# power.net
KiCad netlist of a schematic drawn in Altium Designer
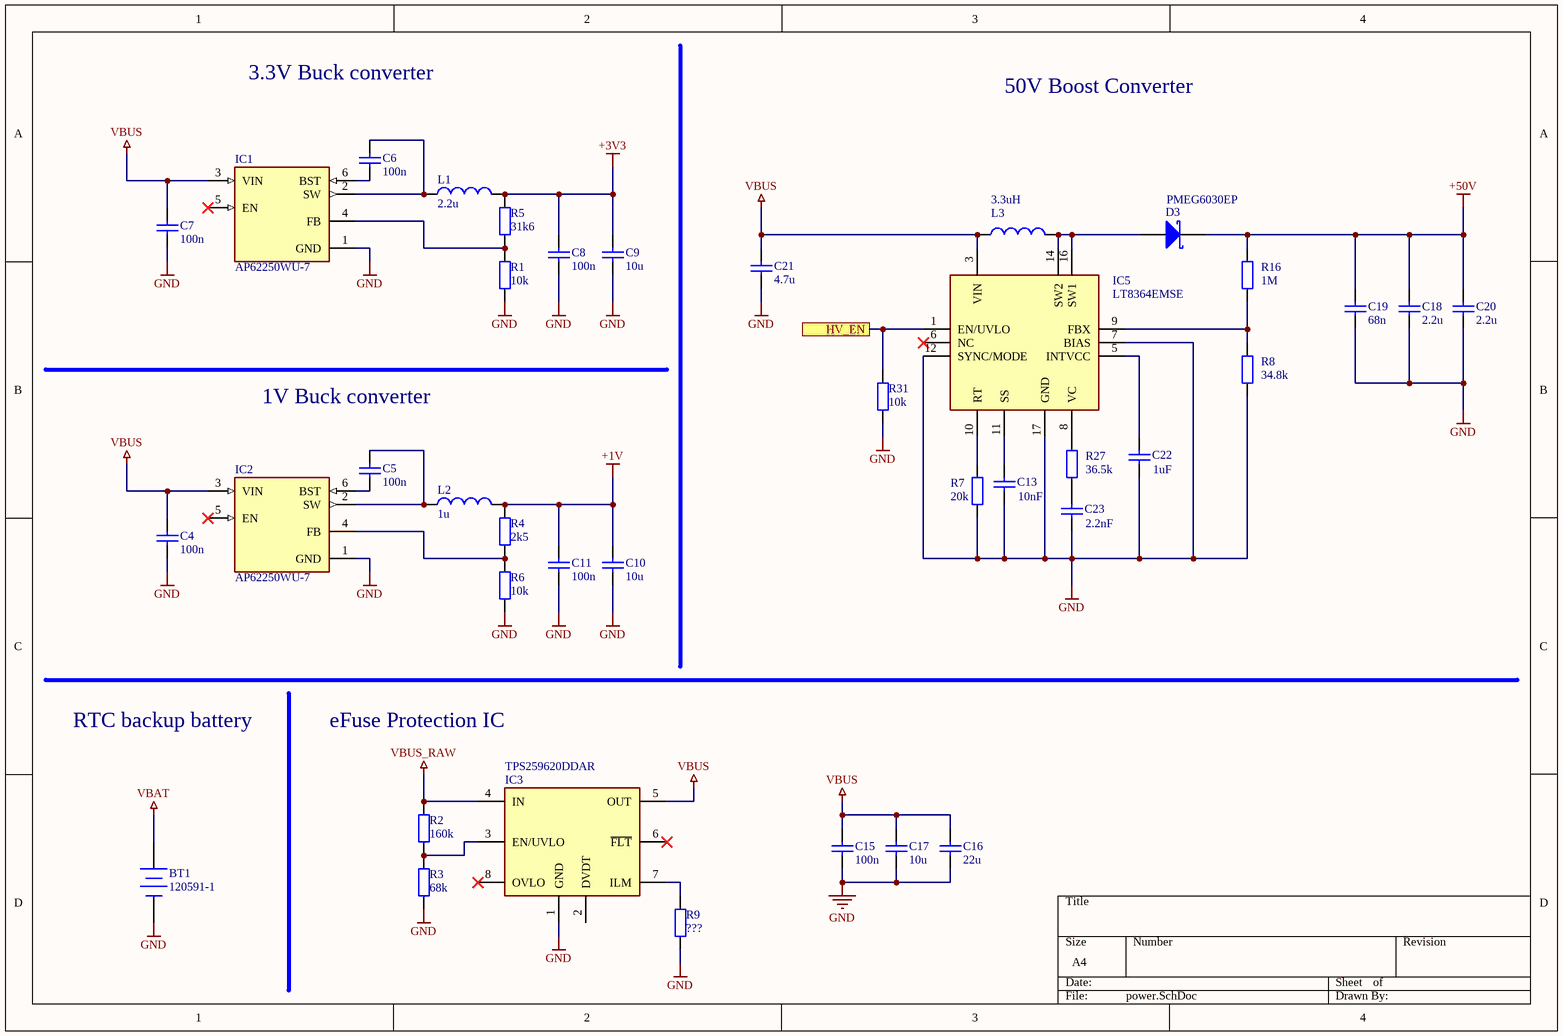
[diagram p0: power.SchDoc]

(export (version "E")
  (design (tool "Eeschema 10.0.6"))
  (components
    (comp (ref "BT1")
      (value "120591-1")
      (footprint "Lib_VFD_Clock:BR1220_Horizontal")
      (description "Battery")
      (fields (field (name "MOUSER PART NUMBER") "571-1205911"))
      (libsource (lib "Lib_VFD_Clock") (part "120591-1"))
    )
    (comp (ref "C4")
      (value "100n")
      (footprint "Miscellaneous Devices:1608[0603]")
      (description "Capacitor")
      (fields (field (name "PUBLISHER") "Altium Limited"))
      (libsource (lib "Miscellaneous Devices") (part "Cap"))
    )
    (comp (ref "C5")
      (value "100n")
      (footprint "Miscellaneous Devices:1608[0603]")
      (description "Capacitor")
      (fields (field (name "PUBLISHER") "Altium Limited"))
      (libsource (lib "Miscellaneous Devices") (part "Cap"))
    )
    (comp (ref "C6")
      (value "100n")
      (footprint "Miscellaneous Devices:1608[0603]")
      (description "Capacitor")
      (fields (field (name "PUBLISHER") "Altium Limited"))
      (libsource (lib "Miscellaneous Devices") (part "Cap"))
    )
    (comp (ref "C7")
      (value "100n")
      (footprint "Miscellaneous Devices:1608[0603]")
      (description "Capacitor")
      (fields (field (name "PUBLISHER") "Altium Limited"))
      (libsource (lib "Miscellaneous Devices") (part "Cap"))
    )
    (comp (ref "C8")
      (value "100n")
      (footprint "Miscellaneous Devices:1608[0603]")
      (description "Capacitor")
      (fields (field (name "PUBLISHER") "Altium Limited"))
      (libsource (lib "Miscellaneous Devices") (part "Cap"))
    )
    (comp (ref "C9")
      (value "10u")
      (footprint "Miscellaneous Devices:1608[0603]")
      (description "Capacitor")
      (fields (field (name "PUBLISHER") "Altium Limited"))
      (libsource (lib "Miscellaneous Devices") (part "Cap"))
    )
    (comp (ref "C10")
      (value "10u")
      (footprint "Miscellaneous Devices:1608[0603]")
      (description "Capacitor")
      (fields (field (name "PUBLISHER") "Altium Limited"))
      (libsource (lib "Miscellaneous Devices") (part "Cap"))
    )
    (comp (ref "C11")
      (value "100n")
      (footprint "Miscellaneous Devices:1608[0603]")
      (description "Capacitor")
      (fields (field (name "PUBLISHER") "Altium Limited"))
      (libsource (lib "Miscellaneous Devices") (part "Cap"))
    )
    (comp (ref "C13")
      (value "10nF")
      (footprint "Miscellaneous Devices:1608[0603]")
      (description "Capacitor")
      (fields (field (name "PUBLISHER") "Altium Limited"))
      (libsource (lib "Miscellaneous Devices") (part "Cap"))
    )
    (comp (ref "C15")
      (value "100n")
      (footprint "Miscellaneous Devices:1608[0603]")
      (description "Capacitor")
      (fields (field (name "PUBLISHER") "Altium Limited"))
      (libsource (lib "Miscellaneous Devices") (part "Cap"))
    )
    (comp (ref "C16")
      (value "22u")
      (footprint "Miscellaneous Devices:1608[0603]")
      (description "Capacitor")
      (fields (field (name "PUBLISHER") "Altium Limited"))
      (libsource (lib "Miscellaneous Devices") (part "Cap"))
    )
    (comp (ref "C17")
      (value "10u")
      (footprint "Miscellaneous Devices:1608[0603]")
      (description "Capacitor")
      (fields (field (name "PUBLISHER") "Altium Limited"))
      (libsource (lib "Miscellaneous Devices") (part "Cap"))
    )
    (comp (ref "C18")
      (value "2.2u")
      (footprint "Miscellaneous Devices:C1210")
      (description "Capacitor")
      (fields (field (name "PUBLISHER") "Altium Limited"))
      (libsource (lib "Miscellaneous Devices") (part "Cap"))
    )
    (comp (ref "C19")
      (value "68n")
      (footprint "Miscellaneous Devices:1608[0603]")
      (description "Capacitor")
      (fields (field (name "PUBLISHER") "Altium Limited"))
      (libsource (lib "Miscellaneous Devices") (part "Cap"))
    )
    (comp (ref "C20")
      (value "2.2u")
      (footprint "Miscellaneous Devices:C1210")
      (description "Capacitor")
      (fields (field (name "PUBLISHER") "Altium Limited"))
      (libsource (lib "Miscellaneous Devices") (part "Cap"))
    )
    (comp (ref "C21")
      (value "4.7u")
      (footprint "Miscellaneous Devices:1608[0603]")
      (description "Capacitor")
      (fields (field (name "PUBLISHER") "Altium Limited"))
      (libsource (lib "Miscellaneous Devices") (part "Cap"))
    )
    (comp (ref "C22")
      (value "1uF")
      (footprint "Miscellaneous Devices:1608[0603]")
      (description "Capacitor")
      (fields (field (name "PUBLISHER") "Altium Limited"))
      (libsource (lib "Miscellaneous Devices") (part "Cap"))
    )
    (comp (ref "C23")
      (value "2.2nF")
      (footprint "Miscellaneous Devices:1608[0603]")
      (description "Capacitor")
      (fields (field (name "PUBLISHER") "Altium Limited"))
      (libsource (lib "Miscellaneous Devices") (part "Cap"))
    )
    (comp (ref "D3")
      (value "PMEG6030EP")
      (footprint "PMEG6030EP115")
      (description "Schottky Diode")
      (fields (field (name "PUBLISHER") "Altium Limited"))
      (libsource (lib "Lib_VFD_Clock") (part "PMEG6030EP"))
    )
    (comp (ref "IC1")
      (value "AP62250WU-7")
      (footprint "TSOT26")
      (description "Integrated Circuit")
      (fields (field (name "MOUSER PART NUMBER") "621-AP62250WU-7"))
      (libsource (lib "Lib_VFD_Clock") (part "AP62250WU-7"))
    )
    (comp (ref "IC2")
      (value "AP62250WU-7")
      (footprint "TSOT26")
      (description "Integrated Circuit")
      (fields (field (name "MOUSER PART NUMBER") "621-AP62250WU-7"))
      (libsource (lib "Lib_VFD_Clock") (part "AP62250WU-7"))
    )
    (comp (ref "IC3")
      (value "TPS259620DDAR")
      (footprint "Lib_VFD_Clock:SOIC127P600X170-9N")
      (description "Integrated Circuit")
      (fields (field (name "MOUSER PART NUMBER") "595-TPS259620DDAR"))
      (libsource (lib "Lib_VFD_Clock") (part "TPS259620DDAR"))
    )
    (comp (ref "IC5")
      (value "LT8364EMSE")
      (footprint "Lib_VFD_Clock:LT8364EMSEPBF")
      (description "Integrated Circuit")
      (fields
        (field (name "MANUFACTURER_PART_NUMBER") "LT8364EMSE#PBF")
        (field (name "MOUSER PART NUMBER") "584-LT8364EMSEPBF")
      )
      (libsource (lib "Lib_VFD_Clock") (part "LT8364EMSE#PBF"))
    )
    (comp (ref "L1")
      (value "2.2u")
      (footprint "Lib_VFD_Clock:BWVS004040182R2M00")
      (description "Inductor")
      (fields (field (name "PUBLISHER") "Altium Limited"))
      (libsource (lib "Miscellaneous Devices") (part "Inductor"))
    )
    (comp (ref "L2")
      (value "1u")
      (footprint "Lib_VFD_Clock:BWVS004040182R2M00")
      (description "Inductor")
      (fields (field (name "PUBLISHER") "Altium Limited"))
      (libsource (lib "Miscellaneous Devices") (part "Inductor"))
    )
    (comp (ref "L3")
      (value "3.3uH")
      (footprint "Lib_VFD_Clock:BWVS004040182R2M00")
      (description "Inductor")
      (fields (field (name "PUBLISHER") "Altium Limited"))
      (libsource (lib "Miscellaneous Devices") (part "Inductor"))
    )
    (comp (ref "R1")
      (value "10k")
      (footprint "Miscellaneous Devices:J1-0603")
      (description "Resistor")
      (fields (field (name "PUBLISHER") "Altium Limited"))
      (libsource (lib "Miscellaneous Devices") (part "Res2"))
    )
    (comp (ref "R2")
      (value "160k")
      (footprint "Miscellaneous Devices:J1-0603")
      (description "Resistor")
      (fields (field (name "PUBLISHER") "Altium Limited"))
      (libsource (lib "Miscellaneous Devices") (part "Res2"))
    )
    (comp (ref "R3")
      (value "68k")
      (footprint "Miscellaneous Devices:J1-0603")
      (description "Resistor")
      (fields (field (name "PUBLISHER") "Altium Limited"))
      (libsource (lib "Miscellaneous Devices") (part "Res2"))
    )
    (comp (ref "R4")
      (value "2k5")
      (footprint "Miscellaneous Devices:J1-0603")
      (description "Resistor")
      (fields (field (name "PUBLISHER") "Altium Limited"))
      (libsource (lib "Miscellaneous Devices") (part "Res2"))
    )
    (comp (ref "R5")
      (value "31k6")
      (footprint "Miscellaneous Devices:J1-0603")
      (description "Resistor")
      (fields (field (name "PUBLISHER") "Altium Limited"))
      (libsource (lib "Miscellaneous Devices") (part "Res2"))
    )
    (comp (ref "R6")
      (value "10k")
      (footprint "Miscellaneous Devices:J1-0603")
      (description "Resistor")
      (fields (field (name "PUBLISHER") "Altium Limited"))
      (libsource (lib "Miscellaneous Devices") (part "Res2"))
    )
    (comp (ref "R7")
      (value "20k")
      (footprint "Miscellaneous Devices:J1-0603")
      (description "Resistor")
      (fields (field (name "PUBLISHER") "Altium Limited"))
      (libsource (lib "Miscellaneous Devices") (part "Res2"))
    )
    (comp (ref "R8")
      (value "34.8k")
      (footprint "Miscellaneous Devices:J1-0603")
      (description "Resistor")
      (fields (field (name "PUBLISHER") "Altium Limited"))
      (libsource (lib "Miscellaneous Devices") (part "Res2"))
    )
    (comp (ref "R9")
      (value "???")
      (footprint "Miscellaneous Devices:J1-0603")
      (description "Resistor")
      (fields (field (name "PUBLISHER") "Altium Limited"))
      (libsource (lib "Miscellaneous Devices") (part "Res2"))
    )
    (comp (ref "R16")
      (value "1M")
      (footprint "Miscellaneous Devices:J1-0603")
      (description "Resistor")
      (fields (field (name "PUBLISHER") "Altium Limited"))
      (libsource (lib "Miscellaneous Devices") (part "Res2"))
    )
    (comp (ref "R27")
      (value "36.5k")
      (footprint "Miscellaneous Devices:J1-0603")
      (description "Resistor")
      (fields (field (name "PUBLISHER") "Altium Limited"))
      (libsource (lib "Miscellaneous Devices") (part "Res2"))
    )
    (comp (ref "R31")
      (value "10k")
      (footprint "Miscellaneous Devices:J1-0603")
      (description "Resistor")
      (fields (field (name "PUBLISHER") "Altium Limited"))
      (libsource (lib "Miscellaneous Devices") (part "Res2"))
    )
  )
  (nets
    (net (code "1") (name "+1V") (class "Default")
      (node (ref "C10") (pin "2") (pinfunction "2_2") (pintype "passive"))
      (node (ref "C11") (pin "2") (pinfunction "2_2") (pintype "passive"))
      (node (ref "L2") (pin "2") (pinfunction "2_2") (pintype "passive"))
      (node (ref "R4") (pin "2") (pinfunction "2_2") (pintype "passive"))
    )
    (net (code "2") (name "+3V3") (class "Default")
      (node (ref "C8") (pin "2") (pinfunction "2_2") (pintype "passive"))
      (node (ref "C9") (pin "2") (pinfunction "2_2") (pintype "passive"))
      (node (ref "L1") (pin "2") (pinfunction "2_2") (pintype "passive"))
      (node (ref "R5") (pin "2") (pinfunction "2_2") (pintype "passive"))
    )
    (net (code "3") (name "+50V") (class "Default")
      (node (ref "C18") (pin "2") (pinfunction "2_2") (pintype "passive"))
      (node (ref "C19") (pin "2") (pinfunction "2_2") (pintype "passive"))
      (node (ref "C20") (pin "2") (pinfunction "2_2") (pintype "passive"))
      (node (ref "D3") (pin "2") (pinfunction "K_2") (pintype "passive"))
      (node (ref "R16") (pin "2") (pinfunction "2_2") (pintype "passive"))
    )
    (net (code "4") (name "/HV_EN") (class "Default")
      (node (ref "IC5") (pin "1") (pinfunction "EN/UVLO_1") (pintype "passive"))
      (node (ref "R31") (pin "2") (pinfunction "2_2") (pintype "passive"))
    )
    (net (code "5") (name "GND") (class "Default")
      (node (ref "BT1") (pin "1") (pinfunction "1_1") (pintype "passive"))
      (node (ref "C10") (pin "1") (pinfunction "1_1") (pintype "passive"))
      (node (ref "C11") (pin "1") (pinfunction "1_1") (pintype "passive"))
      (node (ref "C13") (pin "1") (pinfunction "1_1") (pintype "passive"))
      (node (ref "C15") (pin "1") (pinfunction "1_1") (pintype "passive"))
      (node (ref "C16") (pin "1") (pinfunction "1_1") (pintype "passive"))
      (node (ref "C17") (pin "1") (pinfunction "1_1") (pintype "passive"))
      (node (ref "C18") (pin "1") (pinfunction "1_1") (pintype "passive"))
      (node (ref "C19") (pin "1") (pinfunction "1_1") (pintype "passive"))
      (node (ref "C20") (pin "1") (pinfunction "1_1") (pintype "passive"))
      (node (ref "C21") (pin "1") (pinfunction "1_1") (pintype "passive"))
      (node (ref "C22") (pin "1") (pinfunction "1_1") (pintype "passive"))
      (node (ref "C23") (pin "1") (pinfunction "1_1") (pintype "passive"))
      (node (ref "C4") (pin "1") (pinfunction "1_1") (pintype "passive"))
      (node (ref "C7") (pin "1") (pinfunction "1_1") (pintype "passive"))
      (node (ref "C8") (pin "1") (pinfunction "1_1") (pintype "passive"))
      (node (ref "C9") (pin "1") (pinfunction "1_1") (pintype "passive"))
      (node (ref "IC1") (pin "1") (pinfunction "GND_1") (pintype "power_in"))
      (node (ref "IC2") (pin "1") (pinfunction "GND_1") (pintype "power_in"))
      (node (ref "IC3") (pin "1") (pinfunction "GND_1") (pintype "passive"))
      (node (ref "IC5") (pin "12") (pinfunction "SYNC/MODE_12") (pintype "passive"))
      (node (ref "IC5") (pin "17") (pinfunction "GND_17") (pintype "passive"))
      (node (ref "IC5") (pin "7") (pinfunction "BIAS_7") (pintype "passive"))
      (node (ref "R1") (pin "1") (pinfunction "1_1") (pintype "passive"))
      (node (ref "R3") (pin "1") (pinfunction "1_1") (pintype "passive"))
      (node (ref "R31") (pin "1") (pinfunction "1_1") (pintype "passive"))
      (node (ref "R6") (pin "1") (pinfunction "1_1") (pintype "passive"))
      (node (ref "R7") (pin "1") (pinfunction "1_1") (pintype "passive"))
      (node (ref "R8") (pin "1") (pinfunction "1_1") (pintype "passive"))
      (node (ref "R9") (pin "1") (pinfunction "1_1") (pintype "passive"))
    )
    (net (code "6") (name "Net-(C23-Pad2)") (class "Default")
      (node (ref "C23") (pin "2") (pinfunction "2_2") (pintype "passive"))
      (node (ref "R27") (pin "1") (pinfunction "1_1") (pintype "passive"))
    )
    (net (code "7") (name "Net-(D3-A)") (class "Default")
      (node (ref "D3") (pin "1") (pinfunction "A_1") (pintype "passive"))
      (node (ref "IC5") (pin "14") (pinfunction "SW2_14") (pintype "passive"))
      (node (ref "IC5") (pin "16") (pinfunction "SW1_16") (pintype "passive"))
      (node (ref "L3") (pin "2") (pinfunction "2_2") (pintype "passive"))
    )
    (net (code "8") (name "Net-(IC1-BST)") (class "Default")
      (node (ref "C6") (pin "1") (pinfunction "1_1") (pintype "passive"))
      (node (ref "IC1") (pin "6") (pinfunction "BST_6") (pintype "input"))
    )
    (net (code "9") (name "Net-(IC1-FB)") (class "Default")
      (node (ref "IC1") (pin "4") (pinfunction "FB_4") (pintype "passive"))
      (node (ref "R1") (pin "2") (pinfunction "2_2") (pintype "passive"))
      (node (ref "R5") (pin "1") (pinfunction "1_1") (pintype "passive"))
    )
    (net (code "10") (name "Net-(IC1-SW)") (class "Default")
      (node (ref "C6") (pin "2") (pinfunction "2_2") (pintype "passive"))
      (node (ref "IC1") (pin "2") (pinfunction "SW_2") (pintype "output"))
      (node (ref "L1") (pin "1") (pinfunction "1_1") (pintype "passive"))
    )
    (net (code "11") (name "Net-(IC2-BST)") (class "Default")
      (node (ref "C5") (pin "1") (pinfunction "1_1") (pintype "passive"))
      (node (ref "IC2") (pin "6") (pinfunction "BST_6") (pintype "input"))
    )
    (net (code "12") (name "Net-(IC2-FB)") (class "Default")
      (node (ref "IC2") (pin "4") (pinfunction "FB_4") (pintype "passive"))
      (node (ref "R4") (pin "1") (pinfunction "1_1") (pintype "passive"))
      (node (ref "R6") (pin "2") (pinfunction "2_2") (pintype "passive"))
    )
    (net (code "13") (name "Net-(IC2-SW)") (class "Default")
      (node (ref "C5") (pin "2") (pinfunction "2_2") (pintype "passive"))
      (node (ref "IC2") (pin "2") (pinfunction "SW_2") (pintype "output"))
      (node (ref "L2") (pin "1") (pinfunction "1_1") (pintype "passive"))
    )
    (net (code "14") (name "Net-(IC3-EN{slash}UVLO)") (class "Default")
      (node (ref "IC3") (pin "3") (pinfunction "EN/UVLO_3") (pintype "passive"))
      (node (ref "R2") (pin "1") (pinfunction "1_1") (pintype "passive"))
      (node (ref "R3") (pin "2") (pinfunction "2_2") (pintype "passive"))
    )
    (net (code "15") (name "Net-(IC3-ILM)") (class "Default")
      (node (ref "IC3") (pin "7") (pinfunction "ILM_7") (pintype "passive"))
      (node (ref "R9") (pin "2") (pinfunction "2_2") (pintype "passive"))
    )
    (net (code "16") (name "Net-(IC5-FBX)") (class "Default")
      (node (ref "IC5") (pin "9") (pinfunction "FBX_9") (pintype "passive"))
      (node (ref "R16") (pin "1") (pinfunction "1_1") (pintype "passive"))
      (node (ref "R8") (pin "2") (pinfunction "2_2") (pintype "passive"))
    )
    (net (code "17") (name "Net-(IC5-INTVCC)") (class "Default")
      (node (ref "C22") (pin "2") (pinfunction "2_2") (pintype "passive"))
      (node (ref "IC5") (pin "5") (pinfunction "INTVCC_5") (pintype "passive"))
    )
    (net (code "18") (name "Net-(IC5-RT)") (class "Default")
      (node (ref "IC5") (pin "10") (pinfunction "RT_10") (pintype "passive"))
      (node (ref "R7") (pin "2") (pinfunction "2_2") (pintype "passive"))
    )
    (net (code "19") (name "Net-(IC5-SS)") (class "Default")
      (node (ref "C13") (pin "2") (pinfunction "2_2") (pintype "passive"))
      (node (ref "IC5") (pin "11") (pinfunction "SS_11") (pintype "passive"))
    )
    (net (code "20") (name "Net-(IC5-VC)") (class "Default")
      (node (ref "IC5") (pin "8") (pinfunction "VC_8") (pintype "passive"))
      (node (ref "R27") (pin "2") (pinfunction "2_2") (pintype "passive"))
    )
    (net (code "21") (name "VBAT") (class "Default")
      (node (ref "BT1") (pin "2") (pinfunction "2_2") (pintype "passive"))
    )
    (net (code "22") (name "VBUS") (class "Default")
      (node (ref "C15") (pin "2") (pinfunction "2_2") (pintype "passive"))
      (node (ref "C16") (pin "2") (pinfunction "2_2") (pintype "passive"))
      (node (ref "C17") (pin "2") (pinfunction "2_2") (pintype "passive"))
      (node (ref "C21") (pin "2") (pinfunction "2_2") (pintype "passive"))
      (node (ref "C4") (pin "2") (pinfunction "2_2") (pintype "passive"))
      (node (ref "C7") (pin "2") (pinfunction "2_2") (pintype "passive"))
      (node (ref "IC1") (pin "3") (pinfunction "VIN_3") (pintype "input"))
      (node (ref "IC2") (pin "3") (pinfunction "VIN_3") (pintype "input"))
      (node (ref "IC3") (pin "5") (pinfunction "OUT_5") (pintype "passive"))
      (node (ref "IC5") (pin "3") (pinfunction "VIN_3") (pintype "passive"))
      (node (ref "L3") (pin "1") (pinfunction "1_1") (pintype "passive"))
    )
    (net (code "23") (name "VBUS_RAW") (class "Default")
      (node (ref "IC3") (pin "4") (pinfunction "IN_4") (pintype "passive"))
      (node (ref "R2") (pin "2") (pinfunction "2_2") (pintype "passive"))
    )
    (net (code "24") (name "unconnected-(IC1-EN-Pad5)") (class "Default")
      (node (ref "IC1") (pin "5") (pinfunction "EN_5") (pintype "input+no_connect"))
    )
    (net (code "25") (name "unconnected-(IC2-EN-Pad5)") (class "Default")
      (node (ref "IC2") (pin "5") (pinfunction "EN_5") (pintype "input+no_connect"))
    )
    (net (code "26") (name "unconnected-(IC3-DVDT-Pad2)") (class "Default")
      (node (ref "IC3") (pin "2") (pinfunction "DVDT_2") (pintype "passive"))
    )
    (net (code "27") (name "unconnected-(IC3-OVLO-Pad8)") (class "Default")
      (node (ref "IC3") (pin "8") (pinfunction "OVLO_8") (pintype "passive+no_connect"))
    )
    (net (code "28") (name "unconnected-(IC3-~{FLT}-Pad6)") (class "Default")
      (node (ref "IC3") (pin "6") (pinfunction "~{FLT}_6") (pintype "passive+no_connect"))
    )
    (net (code "29") (name "unconnected-(IC5-NC-Pad6)") (class "Default")
      (node (ref "IC5") (pin "6") (pinfunction "NC_6") (pintype "passive+no_connect"))
    )
  )
)
